# LightRetaggioSchema.net
KiCad netlist of a schematic drawn in EAGLE
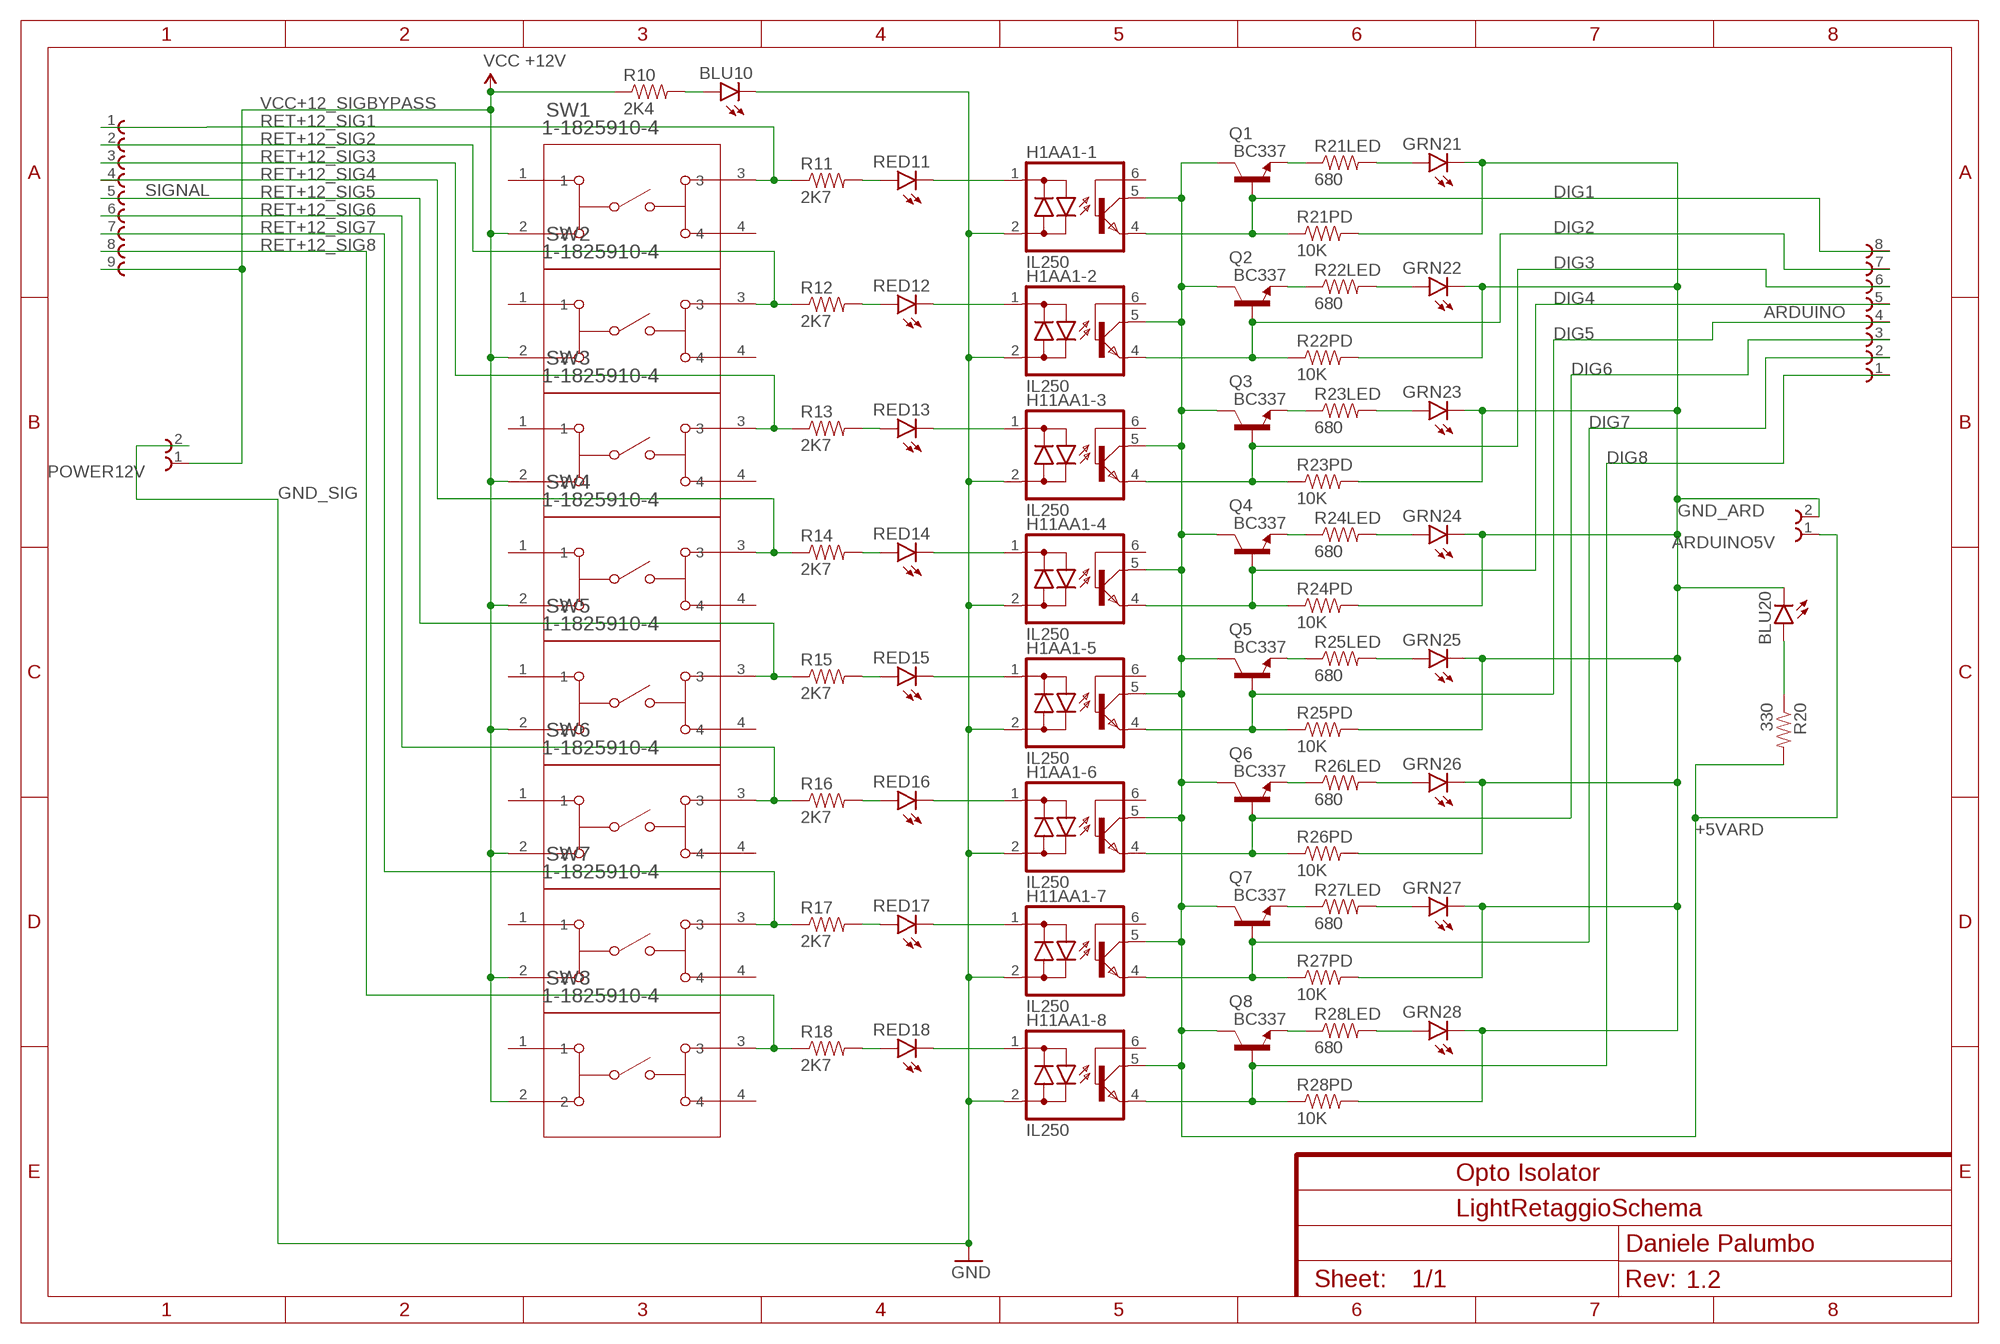
[diagram p0: schematic, sheet 1]

(export (version "E")
  (design (tool "Eeschema 10.0.6"))
  (components
    (comp (ref "ARDUINO")
      (value "691311500108")
      (footprint "eagle-import:691311500108")
      (libsource (lib "eagle-import") (part "691311500108"))
    )
    (comp (ref "ARDUINO5V")
      (value "691311500102")
      (footprint "eagle-import:691311500102")
      (fields (field (name "MF") "WURTH ELEKTRONIK"))
      (libsource (lib "eagle-import") (part "691311500102"))
    )
    (comp (ref "BLU10")
      (value "LED5MM")
      (footprint "eagle-import:LED5MM")
      (fields (field (name "MF") "ALCOSWITCH - TE CONNECTIVITY") (field (name "MPN") "FSM8JH"))
      (libsource (lib "eagle-import") (part "LED5MM"))
    )
    (comp (ref "BLU20")
      (value "LED5MM")
      (footprint "eagle-import:LED5MM")
      (fields (field (name "MF") "ALCOSWITCH - TE CONNECTIVITY") (field (name "MPN") "FSM8JH"))
      (libsource (lib "eagle-import") (part "LED5MM"))
    )
    (comp (ref "GRN21")
      (value "LED5MM")
      (footprint "eagle-import:LED5MM")
      (fields (field (name "MF") "ALCOSWITCH - TE CONNECTIVITY") (field (name "MPN") "FSM8JH"))
      (libsource (lib "eagle-import") (part "LED5MM"))
    )
    (comp (ref "GRN22")
      (value "LED5MM")
      (footprint "eagle-import:LED5MM")
      (fields (field (name "MF") "ALCOSWITCH - TE CONNECTIVITY") (field (name "MPN") "FSM8JH"))
      (libsource (lib "eagle-import") (part "LED5MM"))
    )
    (comp (ref "GRN23")
      (value "LED5MM")
      (footprint "eagle-import:LED5MM")
      (fields (field (name "MF") "ALCOSWITCH - TE CONNECTIVITY") (field (name "MPN") "FSM8JH"))
      (libsource (lib "eagle-import") (part "LED5MM"))
    )
    (comp (ref "GRN24")
      (value "LED5MM")
      (footprint "eagle-import:LED5MM")
      (fields (field (name "MF") "ALCOSWITCH - TE CONNECTIVITY") (field (name "MPN") "FSM8JH"))
      (libsource (lib "eagle-import") (part "LED5MM"))
    )
    (comp (ref "GRN25")
      (value "LED5MM")
      (footprint "eagle-import:LED5MM")
      (fields (field (name "MF") "ALCOSWITCH - TE CONNECTIVITY") (field (name "MPN") "FSM8JH"))
      (libsource (lib "eagle-import") (part "LED5MM"))
    )
    (comp (ref "GRN26")
      (value "LED5MM")
      (footprint "eagle-import:LED5MM")
      (fields (field (name "MF") "ALCOSWITCH - TE CONNECTIVITY") (field (name "MPN") "FSM8JH"))
      (libsource (lib "eagle-import") (part "LED5MM"))
    )
    (comp (ref "GRN27")
      (value "LED5MM")
      (footprint "eagle-import:LED5MM")
      (fields (field (name "MF") "ALCOSWITCH - TE CONNECTIVITY") (field (name "MPN") "FSM8JH"))
      (libsource (lib "eagle-import") (part "LED5MM"))
    )
    (comp (ref "GRN28")
      (value "LED5MM")
      (footprint "eagle-import:LED5MM")
      (fields (field (name "MF") "ALCOSWITCH - TE CONNECTIVITY") (field (name "MPN") "FSM8JH"))
      (libsource (lib "eagle-import") (part "LED5MM"))
    )
    (comp (ref "H1AA1-1")
      (value "IL250")
      (footprint "eagle-import:DIL06")
      (fields (field (name "MF") "VISHAY/TELEFUNKEN") (field (name "OC_FARNELL") "unknown"))
      (libsource (lib "eagle-import") (part "IL250"))
    )
    (comp (ref "H1AA1-2")
      (value "IL250")
      (footprint "eagle-import:DIL06")
      (fields (field (name "MF") "VISHAY/TELEFUNKEN") (field (name "OC_FARNELL") "unknown"))
      (libsource (lib "eagle-import") (part "IL250"))
    )
    (comp (ref "H1AA1-5")
      (value "IL250")
      (footprint "eagle-import:DIL06")
      (fields (field (name "MF") "VISHAY/TELEFUNKEN") (field (name "OC_FARNELL") "unknown"))
      (libsource (lib "eagle-import") (part "IL250"))
    )
    (comp (ref "H1AA1-6")
      (value "IL250")
      (footprint "eagle-import:DIL06")
      (fields (field (name "MF") "VISHAY/TELEFUNKEN") (field (name "OC_FARNELL") "unknown"))
      (libsource (lib "eagle-import") (part "IL250"))
    )
    (comp (ref "H11AA1-3")
      (value "IL250")
      (footprint "eagle-import:DIL06")
      (fields (field (name "MF") "VISHAY/TELEFUNKEN") (field (name "OC_FARNELL") "unknown"))
      (libsource (lib "eagle-import") (part "IL250"))
    )
    (comp (ref "H11AA1-4")
      (value "IL250")
      (footprint "eagle-import:DIL06")
      (fields (field (name "MF") "VISHAY/TELEFUNKEN") (field (name "OC_FARNELL") "unknown"))
      (libsource (lib "eagle-import") (part "IL250"))
    )
    (comp (ref "H11AA1-7")
      (value "IL250")
      (footprint "eagle-import:DIL06")
      (fields (field (name "MF") "VISHAY/TELEFUNKEN") (field (name "OC_FARNELL") "unknown"))
      (libsource (lib "eagle-import") (part "IL250"))
    )
    (comp (ref "H11AA1-8")
      (value "IL250")
      (footprint "eagle-import:DIL06")
      (fields (field (name "MF") "VISHAY/TELEFUNKEN") (field (name "OC_FARNELL") "unknown"))
      (libsource (lib "eagle-import") (part "IL250"))
    )
    (comp (ref "POWER12V")
      (value "691311500102")
      (footprint "eagle-import:691311500102")
      (fields (field (name "MF") "WURTH ELEKTRONIK"))
      (libsource (lib "eagle-import") (part "691311500102"))
    )
    (comp (ref "Q1")
      (value "BC337")
      (footprint "eagle-import:TO-92")
      (libsource (lib "eagle-import") (part "TRANS_NPN-P2N2222A"))
    )
    (comp (ref "Q2")
      (value "BC337")
      (footprint "eagle-import:TO-92")
      (libsource (lib "eagle-import") (part "TRANS_NPN-P2N2222A"))
    )
    (comp (ref "Q3")
      (value "BC337")
      (footprint "eagle-import:TO-92")
      (libsource (lib "eagle-import") (part "TRANS_NPN-P2N2222A"))
    )
    (comp (ref "Q4")
      (value "BC337")
      (footprint "eagle-import:TO-92")
      (libsource (lib "eagle-import") (part "TRANS_NPN-P2N2222A"))
    )
    (comp (ref "Q5")
      (value "BC337")
      (footprint "eagle-import:TO-92")
      (libsource (lib "eagle-import") (part "TRANS_NPN-P2N2222A"))
    )
    (comp (ref "Q6")
      (value "BC337")
      (footprint "eagle-import:TO-92")
      (libsource (lib "eagle-import") (part "TRANS_NPN-P2N2222A"))
    )
    (comp (ref "Q7")
      (value "BC337")
      (footprint "eagle-import:TO-92")
      (libsource (lib "eagle-import") (part "TRANS_NPN-P2N2222A"))
    )
    (comp (ref "Q8")
      (value "BC337")
      (footprint "eagle-import:TO-92")
      (libsource (lib "eagle-import") (part "TRANS_NPN-P2N2222A"))
    )
    (comp (ref "R10")
      (value "2K4")
      (footprint "eagle-import:AXIAL-0.4")
      (libsource (lib "eagle-import") (part "RESISTORPTH-1/4W"))
    )
    (comp (ref "R11")
      (value "2K7")
      (footprint "eagle-import:AXIAL-0.4")
      (libsource (lib "eagle-import") (part "RESISTORPTH-1/4W"))
    )
    (comp (ref "R12")
      (value "2K7")
      (footprint "eagle-import:AXIAL-0.4")
      (libsource (lib "eagle-import") (part "RESISTORPTH-1/4W"))
    )
    (comp (ref "R13")
      (value "2K7")
      (footprint "eagle-import:AXIAL-0.4")
      (libsource (lib "eagle-import") (part "RESISTORPTH-1/4W"))
    )
    (comp (ref "R14")
      (value "2K7")
      (footprint "eagle-import:AXIAL-0.4")
      (libsource (lib "eagle-import") (part "RESISTORPTH-1/4W"))
    )
    (comp (ref "R15")
      (value "2K7")
      (footprint "eagle-import:AXIAL-0.4")
      (libsource (lib "eagle-import") (part "RESISTORPTH-1/4W"))
    )
    (comp (ref "R16")
      (value "2K7")
      (footprint "eagle-import:AXIAL-0.4")
      (libsource (lib "eagle-import") (part "RESISTORPTH-1/4W"))
    )
    (comp (ref "R17")
      (value "2K7")
      (footprint "eagle-import:AXIAL-0.4")
      (libsource (lib "eagle-import") (part "RESISTORPTH-1/4W"))
    )
    (comp (ref "R18")
      (value "2K7")
      (footprint "eagle-import:AXIAL-0.4")
      (libsource (lib "eagle-import") (part "RESISTORPTH-1/4W"))
    )
    (comp (ref "R20")
      (value "330")
      (footprint "eagle-import:AXIAL-0.4")
      (libsource (lib "eagle-import") (part "RESISTORPTH-1/4W"))
    )
    (comp (ref "R21LED")
      (value "680")
      (footprint "eagle-import:AXIAL-0.4")
      (libsource (lib "eagle-import") (part "RESISTORPTH-1/4W"))
    )
    (comp (ref "R21PD")
      (value "10K")
      (footprint "eagle-import:AXIAL-0.4")
      (libsource (lib "eagle-import") (part "RESISTORPTH-1/4W"))
    )
    (comp (ref "R22LED")
      (value "680")
      (footprint "eagle-import:AXIAL-0.4")
      (libsource (lib "eagle-import") (part "RESISTORPTH-1/4W"))
    )
    (comp (ref "R22PD")
      (value "10K")
      (footprint "eagle-import:AXIAL-0.4")
      (libsource (lib "eagle-import") (part "RESISTORPTH-1/4W"))
    )
    (comp (ref "R23LED")
      (value "680")
      (footprint "eagle-import:AXIAL-0.4")
      (libsource (lib "eagle-import") (part "RESISTORPTH-1/4W"))
    )
    (comp (ref "R23PD")
      (value "10K")
      (footprint "eagle-import:AXIAL-0.4")
      (libsource (lib "eagle-import") (part "RESISTORPTH-1/4W"))
    )
    (comp (ref "R24LED")
      (value "680")
      (footprint "eagle-import:AXIAL-0.4")
      (libsource (lib "eagle-import") (part "RESISTORPTH-1/4W"))
    )
    (comp (ref "R24PD")
      (value "10K")
      (footprint "eagle-import:AXIAL-0.4")
      (libsource (lib "eagle-import") (part "RESISTORPTH-1/4W"))
    )
    (comp (ref "R25LED")
      (value "680")
      (footprint "eagle-import:AXIAL-0.4")
      (libsource (lib "eagle-import") (part "RESISTORPTH-1/4W"))
    )
    (comp (ref "R25PD")
      (value "10K")
      (footprint "eagle-import:AXIAL-0.4")
      (libsource (lib "eagle-import") (part "RESISTORPTH-1/4W"))
    )
    (comp (ref "R26LED")
      (value "680")
      (footprint "eagle-import:AXIAL-0.4")
      (libsource (lib "eagle-import") (part "RESISTORPTH-1/4W"))
    )
    (comp (ref "R26PD")
      (value "10K")
      (footprint "eagle-import:AXIAL-0.4")
      (libsource (lib "eagle-import") (part "RESISTORPTH-1/4W"))
    )
    (comp (ref "R27LED")
      (value "680")
      (footprint "eagle-import:AXIAL-0.4")
      (libsource (lib "eagle-import") (part "RESISTORPTH-1/4W"))
    )
    (comp (ref "R27PD")
      (value "10K")
      (footprint "eagle-import:AXIAL-0.4")
      (libsource (lib "eagle-import") (part "RESISTORPTH-1/4W"))
    )
    (comp (ref "R28LED")
      (value "680")
      (footprint "eagle-import:AXIAL-0.4")
      (libsource (lib "eagle-import") (part "RESISTORPTH-1/4W"))
    )
    (comp (ref "R28PD")
      (value "10K")
      (footprint "eagle-import:AXIAL-0.4")
      (libsource (lib "eagle-import") (part "RESISTORPTH-1/4W"))
    )
    (comp (ref "RED11")
      (value "LED5MM")
      (footprint "eagle-import:LED5MM")
      (fields (field (name "MF") "ALCOSWITCH - TE CONNECTIVITY") (field (name "MPN") "FSM8JH"))
      (libsource (lib "eagle-import") (part "LED5MM"))
    )
    (comp (ref "RED12")
      (value "LED5MM")
      (footprint "eagle-import:LED5MM")
      (fields (field (name "MF") "ALCOSWITCH - TE CONNECTIVITY") (field (name "MPN") "FSM8JH"))
      (libsource (lib "eagle-import") (part "LED5MM"))
    )
    (comp (ref "RED13")
      (value "LED5MM")
      (footprint "eagle-import:LED5MM")
      (fields (field (name "MF") "ALCOSWITCH - TE CONNECTIVITY") (field (name "MPN") "FSM8JH"))
      (libsource (lib "eagle-import") (part "LED5MM"))
    )
    (comp (ref "RED14")
      (value "LED5MM")
      (footprint "eagle-import:LED5MM")
      (fields (field (name "MF") "ALCOSWITCH - TE CONNECTIVITY") (field (name "MPN") "FSM8JH"))
      (libsource (lib "eagle-import") (part "LED5MM"))
    )
    (comp (ref "RED15")
      (value "LED5MM")
      (footprint "eagle-import:LED5MM")
      (fields (field (name "MF") "ALCOSWITCH - TE CONNECTIVITY") (field (name "MPN") "FSM8JH"))
      (libsource (lib "eagle-import") (part "LED5MM"))
    )
    (comp (ref "RED16")
      (value "LED5MM")
      (footprint "eagle-import:LED5MM")
      (fields (field (name "MF") "ALCOSWITCH - TE CONNECTIVITY") (field (name "MPN") "FSM8JH"))
      (libsource (lib "eagle-import") (part "LED5MM"))
    )
    (comp (ref "RED17")
      (value "LED5MM")
      (footprint "eagle-import:LED5MM")
      (fields (field (name "MF") "ALCOSWITCH - TE CONNECTIVITY") (field (name "MPN") "FSM8JH"))
      (libsource (lib "eagle-import") (part "LED5MM"))
    )
    (comp (ref "RED18")
      (value "LED5MM")
      (footprint "eagle-import:LED5MM")
      (fields (field (name "MF") "ALCOSWITCH - TE CONNECTIVITY") (field (name "MPN") "FSM8JH"))
      (libsource (lib "eagle-import") (part "LED5MM"))
    )
    (comp (ref "SIGNAL")
      (value "691311500109")
      (footprint "eagle-import:691311500109")
      (libsource (lib "eagle-import") (part "691311500109"))
    )
    (comp (ref "SW1")
      (value "1-1825910-4")
      (footprint "eagle-import:SW4_1825910-D")
      (fields (field (name "COPYRIGHT") "Copyright (C) 2016 Accelerated Designs. All rights reserved"))
      (libsource (lib "eagle-import") (part "1-1825910-4"))
    )
    (comp (ref "SW2")
      (value "1-1825910-4")
      (footprint "eagle-import:SW4_1825910-D")
      (fields (field (name "COPYRIGHT") "Copyright (C) 2016 Accelerated Designs. All rights reserved"))
      (libsource (lib "eagle-import") (part "1-1825910-4"))
    )
    (comp (ref "SW3")
      (value "1-1825910-4")
      (footprint "eagle-import:SW4_1825910-D")
      (fields (field (name "COPYRIGHT") "Copyright (C) 2016 Accelerated Designs. All rights reserved"))
      (libsource (lib "eagle-import") (part "1-1825910-4"))
    )
    (comp (ref "SW4")
      (value "1-1825910-4")
      (footprint "eagle-import:SW4_1825910-D")
      (fields (field (name "COPYRIGHT") "Copyright (C) 2016 Accelerated Designs. All rights reserved"))
      (libsource (lib "eagle-import") (part "1-1825910-4"))
    )
    (comp (ref "SW5")
      (value "1-1825910-4")
      (footprint "eagle-import:SW4_1825910-D")
      (fields (field (name "COPYRIGHT") "Copyright (C) 2016 Accelerated Designs. All rights reserved"))
      (libsource (lib "eagle-import") (part "1-1825910-4"))
    )
    (comp (ref "SW6")
      (value "1-1825910-4")
      (footprint "eagle-import:SW4_1825910-D")
      (fields (field (name "COPYRIGHT") "Copyright (C) 2016 Accelerated Designs. All rights reserved"))
      (libsource (lib "eagle-import") (part "1-1825910-4"))
    )
    (comp (ref "SW7")
      (value "1-1825910-4")
      (footprint "eagle-import:SW4_1825910-D")
      (fields (field (name "COPYRIGHT") "Copyright (C) 2016 Accelerated Designs. All rights reserved"))
      (libsource (lib "eagle-import") (part "1-1825910-4"))
    )
    (comp (ref "SW8")
      (value "1-1825910-4")
      (footprint "eagle-import:SW4_1825910-D")
      (fields (field (name "COPYRIGHT") "Copyright (C) 2016 Accelerated Designs. All rights reserved"))
      (libsource (lib "eagle-import") (part "1-1825910-4"))
    )
  )
  (nets
    (net (code "1") (name "/+5VARD") (class "Default")
      (node (ref "ARDUINO5V") (pin "1") (pinfunction "1_1") (pintype "passive"))
      (node (ref "H11AA1-3") (pin "5") (pinfunction "C_5") (pintype "passive"))
      (node (ref "H11AA1-4") (pin "5") (pinfunction "C_5") (pintype "passive"))
      (node (ref "H11AA1-7") (pin "5") (pinfunction "C_5") (pintype "passive"))
      (node (ref "H11AA1-8") (pin "5") (pinfunction "C_5") (pintype "passive"))
      (node (ref "H1AA1-1") (pin "5") (pinfunction "C_5") (pintype "passive"))
      (node (ref "H1AA1-2") (pin "5") (pinfunction "C_5") (pintype "passive"))
      (node (ref "H1AA1-5") (pin "5") (pinfunction "C_5") (pintype "passive"))
      (node (ref "H1AA1-6") (pin "5") (pinfunction "C_5") (pintype "passive"))
      (node (ref "Q1") (pin "1") (pinfunction "C_1") (pintype "passive"))
      (node (ref "Q2") (pin "1") (pinfunction "C_1") (pintype "passive"))
      (node (ref "Q3") (pin "1") (pinfunction "C_1") (pintype "passive"))
      (node (ref "Q4") (pin "1") (pinfunction "C_1") (pintype "passive"))
      (node (ref "Q5") (pin "1") (pinfunction "C_1") (pintype "passive"))
      (node (ref "Q6") (pin "1") (pinfunction "C_1") (pintype "passive"))
      (node (ref "Q7") (pin "1") (pinfunction "C_1") (pintype "passive"))
      (node (ref "Q8") (pin "1") (pinfunction "C_1") (pintype "passive"))
      (node (ref "R20") (pin "P$2") (pinfunction "2_P$2") (pintype "passive"))
    )
    (net (code "2") (name "/DIG1") (class "Default")
      (node (ref "ARDUINO") (pin "8") (pinfunction "8_8") (pintype "passive"))
      (node (ref "H1AA1-1") (pin "4") (pinfunction "E_4") (pintype "passive"))
      (node (ref "Q1") (pin "2") (pinfunction "B_2") (pintype "passive"))
      (node (ref "R21PD") (pin "P$1") (pinfunction "1_P$1") (pintype "passive"))
    )
    (net (code "3") (name "/DIG2") (class "Default")
      (node (ref "ARDUINO") (pin "7") (pinfunction "7_7") (pintype "passive"))
      (node (ref "H1AA1-2") (pin "4") (pinfunction "E_4") (pintype "passive"))
      (node (ref "Q2") (pin "2") (pinfunction "B_2") (pintype "passive"))
      (node (ref "R22PD") (pin "P$1") (pinfunction "1_P$1") (pintype "passive"))
    )
    (net (code "4") (name "/DIG3") (class "Default")
      (node (ref "ARDUINO") (pin "6") (pinfunction "6_6") (pintype "passive"))
      (node (ref "H11AA1-3") (pin "4") (pinfunction "E_4") (pintype "passive"))
      (node (ref "Q3") (pin "2") (pinfunction "B_2") (pintype "passive"))
      (node (ref "R23PD") (pin "P$1") (pinfunction "1_P$1") (pintype "passive"))
    )
    (net (code "5") (name "/DIG4") (class "Default")
      (node (ref "ARDUINO") (pin "5") (pinfunction "5_5") (pintype "passive"))
      (node (ref "H11AA1-4") (pin "4") (pinfunction "E_4") (pintype "passive"))
      (node (ref "Q4") (pin "2") (pinfunction "B_2") (pintype "passive"))
      (node (ref "R24PD") (pin "P$1") (pinfunction "1_P$1") (pintype "passive"))
    )
    (net (code "6") (name "/DIG5") (class "Default")
      (node (ref "ARDUINO") (pin "4") (pinfunction "4_4") (pintype "passive"))
      (node (ref "H1AA1-5") (pin "4") (pinfunction "E_4") (pintype "passive"))
      (node (ref "Q5") (pin "2") (pinfunction "B_2") (pintype "passive"))
      (node (ref "R25PD") (pin "P$1") (pinfunction "1_P$1") (pintype "passive"))
    )
    (net (code "7") (name "/DIG6") (class "Default")
      (node (ref "ARDUINO") (pin "3") (pinfunction "3_3") (pintype "passive"))
      (node (ref "H1AA1-6") (pin "4") (pinfunction "E_4") (pintype "passive"))
      (node (ref "Q6") (pin "2") (pinfunction "B_2") (pintype "passive"))
      (node (ref "R26PD") (pin "P$1") (pinfunction "1_P$1") (pintype "passive"))
    )
    (net (code "8") (name "/DIG7") (class "Default")
      (node (ref "ARDUINO") (pin "2") (pinfunction "2_2") (pintype "passive"))
      (node (ref "H11AA1-7") (pin "4") (pinfunction "E_4") (pintype "passive"))
      (node (ref "Q7") (pin "2") (pinfunction "B_2") (pintype "passive"))
      (node (ref "R27PD") (pin "P$1") (pinfunction "1_P$1") (pintype "passive"))
    )
    (net (code "9") (name "/DIG8") (class "Default")
      (node (ref "ARDUINO") (pin "1") (pinfunction "1_1") (pintype "passive"))
      (node (ref "H11AA1-8") (pin "4") (pinfunction "E_4") (pintype "passive"))
      (node (ref "Q8") (pin "2") (pinfunction "B_2") (pintype "passive"))
      (node (ref "R28PD") (pin "P$1") (pinfunction "1_P$1") (pintype "passive"))
    )
    (net (code "10") (name "/GND_ARD") (class "Default")
      (node (ref "ARDUINO5V") (pin "2") (pinfunction "2_2") (pintype "passive"))
      (node (ref "BLU20") (pin "K") (pinfunction "C_K") (pintype "passive"))
      (node (ref "GRN21") (pin "K") (pinfunction "C_K") (pintype "passive"))
      (node (ref "GRN22") (pin "K") (pinfunction "C_K") (pintype "passive"))
      (node (ref "GRN23") (pin "K") (pinfunction "C_K") (pintype "passive"))
      (node (ref "GRN24") (pin "K") (pinfunction "C_K") (pintype "passive"))
      (node (ref "GRN25") (pin "K") (pinfunction "C_K") (pintype "passive"))
      (node (ref "GRN26") (pin "K") (pinfunction "C_K") (pintype "passive"))
      (node (ref "GRN27") (pin "K") (pinfunction "C_K") (pintype "passive"))
      (node (ref "GRN28") (pin "K") (pinfunction "C_K") (pintype "passive"))
      (node (ref "R21PD") (pin "P$2") (pinfunction "2_P$2") (pintype "passive"))
      (node (ref "R22PD") (pin "P$2") (pinfunction "2_P$2") (pintype "passive"))
      (node (ref "R23PD") (pin "P$2") (pinfunction "2_P$2") (pintype "passive"))
      (node (ref "R24PD") (pin "P$2") (pinfunction "2_P$2") (pintype "passive"))
      (node (ref "R25PD") (pin "P$2") (pinfunction "2_P$2") (pintype "passive"))
      (node (ref "R26PD") (pin "P$2") (pinfunction "2_P$2") (pintype "passive"))
      (node (ref "R27PD") (pin "P$2") (pinfunction "2_P$2") (pintype "passive"))
      (node (ref "R28PD") (pin "P$2") (pinfunction "2_P$2") (pintype "passive"))
    )
    (net (code "11") (name "/RET+12_SIG1") (class "Default")
      (node (ref "R11") (pin "P$1") (pinfunction "1_P$1") (pintype "passive"))
      (node (ref "SIGNAL") (pin "1") (pinfunction "1_1") (pintype "passive"))
      (node (ref "SW1") (pin "3") (pinfunction "3_3") (pintype "passive"))
    )
    (net (code "12") (name "/RET+12_SIG2") (class "Default")
      (node (ref "R12") (pin "P$1") (pinfunction "1_P$1") (pintype "passive"))
      (node (ref "SIGNAL") (pin "2") (pinfunction "2_2") (pintype "passive"))
      (node (ref "SW2") (pin "3") (pinfunction "3_3") (pintype "passive"))
    )
    (net (code "13") (name "/RET+12_SIG3") (class "Default")
      (node (ref "R13") (pin "P$1") (pinfunction "1_P$1") (pintype "passive"))
      (node (ref "SIGNAL") (pin "3") (pinfunction "3_3") (pintype "passive"))
      (node (ref "SW3") (pin "3") (pinfunction "3_3") (pintype "passive"))
    )
    (net (code "14") (name "/RET+12_SIG4") (class "Default")
      (node (ref "R14") (pin "P$1") (pinfunction "1_P$1") (pintype "passive"))
      (node (ref "SIGNAL") (pin "4") (pinfunction "4_4") (pintype "passive"))
      (node (ref "SW4") (pin "3") (pinfunction "3_3") (pintype "passive"))
    )
    (net (code "15") (name "/RET+12_SIG5") (class "Default")
      (node (ref "R15") (pin "P$1") (pinfunction "1_P$1") (pintype "passive"))
      (node (ref "SIGNAL") (pin "5") (pinfunction "5_5") (pintype "passive"))
      (node (ref "SW5") (pin "3") (pinfunction "3_3") (pintype "passive"))
    )
    (net (code "16") (name "/RET+12_SIG6") (class "Default")
      (node (ref "R16") (pin "P$1") (pinfunction "1_P$1") (pintype "passive"))
      (node (ref "SIGNAL") (pin "6") (pinfunction "6_6") (pintype "passive"))
      (node (ref "SW6") (pin "3") (pinfunction "3_3") (pintype "passive"))
    )
    (net (code "17") (name "/RET+12_SIG7") (class "Default")
      (node (ref "R17") (pin "P$1") (pinfunction "1_P$1") (pintype "passive"))
      (node (ref "SIGNAL") (pin "7") (pinfunction "7_7") (pintype "passive"))
      (node (ref "SW7") (pin "3") (pinfunction "3_3") (pintype "passive"))
    )
    (net (code "18") (name "/RET+12_SIG8") (class "Default")
      (node (ref "R18") (pin "P$1") (pinfunction "1_P$1") (pintype "passive"))
      (node (ref "SIGNAL") (pin "8") (pinfunction "8_8") (pintype "passive"))
      (node (ref "SW8") (pin "3") (pinfunction "3_3") (pintype "passive"))
    )
    (net (code "19") (name "GND") (class "Default")
      (node (ref "BLU10") (pin "K") (pinfunction "C_K") (pintype "passive"))
      (node (ref "H11AA1-3") (pin "2") (pinfunction "AC2_2") (pintype "passive"))
      (node (ref "H11AA1-4") (pin "2") (pinfunction "AC2_2") (pintype "passive"))
      (node (ref "H11AA1-7") (pin "2") (pinfunction "AC2_2") (pintype "passive"))
      (node (ref "H11AA1-8") (pin "2") (pinfunction "AC2_2") (pintype "passive"))
      (node (ref "H1AA1-1") (pin "2") (pinfunction "AC2_2") (pintype "passive"))
      (node (ref "H1AA1-2") (pin "2") (pinfunction "AC2_2") (pintype "passive"))
      (node (ref "H1AA1-5") (pin "2") (pinfunction "AC2_2") (pintype "passive"))
      (node (ref "H1AA1-6") (pin "2") (pinfunction "AC2_2") (pintype "passive"))
      (node (ref "POWER12V") (pin "2") (pinfunction "2_2") (pintype "passive"))
    )
    (net (code "20") (name "Net-(H1AA1-1-AC1)") (class "Default")
      (node (ref "H1AA1-1") (pin "1") (pinfunction "AC1_1") (pintype "passive"))
      (node (ref "RED11") (pin "K") (pinfunction "C_K") (pintype "passive"))
    )
    (net (code "21") (name "Net-(H1AA1-2-AC1)") (class "Default")
      (node (ref "H1AA1-2") (pin "1") (pinfunction "AC1_1") (pintype "passive"))
      (node (ref "RED12") (pin "K") (pinfunction "C_K") (pintype "passive"))
    )
    (net (code "22") (name "Net-(H1AA1-5-AC1)") (class "Default")
      (node (ref "H1AA1-5") (pin "1") (pinfunction "AC1_1") (pintype "passive"))
      (node (ref "RED15") (pin "K") (pinfunction "C_K") (pintype "passive"))
    )
    (net (code "23") (name "Net-(H1AA1-6-AC1)") (class "Default")
      (node (ref "H1AA1-6") (pin "1") (pinfunction "AC1_1") (pintype "passive"))
      (node (ref "RED16") (pin "K") (pinfunction "C_K") (pintype "passive"))
    )
    (net (code "24") (name "Net-(H11AA1-3-AC1)") (class "Default")
      (node (ref "H11AA1-3") (pin "1") (pinfunction "AC1_1") (pintype "passive"))
      (node (ref "RED13") (pin "K") (pinfunction "C_K") (pintype "passive"))
    )
    (net (code "25") (name "Net-(H11AA1-4-AC1)") (class "Default")
      (node (ref "H11AA1-4") (pin "1") (pinfunction "AC1_1") (pintype "passive"))
      (node (ref "RED14") (pin "K") (pinfunction "C_K") (pintype "passive"))
    )
    (net (code "26") (name "Net-(H11AA1-7-AC1)") (class "Default")
      (node (ref "H11AA1-7") (pin "1") (pinfunction "AC1_1") (pintype "passive"))
      (node (ref "RED17") (pin "K") (pinfunction "C_K") (pintype "passive"))
    )
    (net (code "27") (name "Net-(H11AA1-8-AC1)") (class "Default")
      (node (ref "H11AA1-8") (pin "1") (pinfunction "AC1_1") (pintype "passive"))
      (node (ref "RED18") (pin "K") (pinfunction "C_K") (pintype "passive"))
    )
    (net (code "28") (name "Net-(Q1-E)") (class "Default")
      (node (ref "Q1") (pin "3") (pinfunction "E_3") (pintype "passive"))
      (node (ref "R21LED") (pin "P$1") (pinfunction "1_P$1") (pintype "passive"))
    )
    (net (code "29") (name "Net-(Q2-E)") (class "Default")
      (node (ref "Q2") (pin "3") (pinfunction "E_3") (pintype "passive"))
      (node (ref "R22LED") (pin "P$1") (pinfunction "1_P$1") (pintype "passive"))
    )
    (net (code "30") (name "Net-(Q3-E)") (class "Default")
      (node (ref "Q3") (pin "3") (pinfunction "E_3") (pintype "passive"))
      (node (ref "R23LED") (pin "P$1") (pinfunction "1_P$1") (pintype "passive"))
    )
    (net (code "31") (name "Net-(Q4-E)") (class "Default")
      (node (ref "Q4") (pin "3") (pinfunction "E_3") (pintype "passive"))
      (node (ref "R24LED") (pin "P$1") (pinfunction "1_P$1") (pintype "passive"))
    )
    (net (code "32") (name "Net-(Q5-E)") (class "Default")
      (node (ref "Q5") (pin "3") (pinfunction "E_3") (pintype "passive"))
      (node (ref "R25LED") (pin "P$1") (pinfunction "1_P$1") (pintype "passive"))
    )
    (net (code "33") (name "Net-(Q6-E)") (class "Default")
      (node (ref "Q6") (pin "3") (pinfunction "E_3") (pintype "passive"))
      (node (ref "R26LED") (pin "P$1") (pinfunction "1_P$1") (pintype "passive"))
    )
    (net (code "34") (name "Net-(Q7-E)") (class "Default")
      (node (ref "Q7") (pin "3") (pinfunction "E_3") (pintype "passive"))
      (node (ref "R27LED") (pin "P$1") (pinfunction "1_P$1") (pintype "passive"))
    )
    (net (code "35") (name "Net-(Q8-E)") (class "Default")
      (node (ref "Q8") (pin "3") (pinfunction "E_3") (pintype "passive"))
      (node (ref "R28LED") (pin "P$1") (pinfunction "1_P$1") (pintype "passive"))
    )
    (net (code "36") (name "Net-(R10-2)") (class "Default")
      (node (ref "BLU10") (pin "A") (pinfunction "A_A") (pintype "passive"))
      (node (ref "R10") (pin "P$2") (pinfunction "2_P$2") (pintype "passive"))
    )
    (net (code "37") (name "Net-(R11-2)") (class "Default")
      (node (ref "R11") (pin "P$2") (pinfunction "2_P$2") (pintype "passive"))
      (node (ref "RED11") (pin "A") (pinfunction "A_A") (pintype "passive"))
    )
    (net (code "38") (name "Net-(R12-2)") (class "Default")
      (node (ref "R12") (pin "P$2") (pinfunction "2_P$2") (pintype "passive"))
      (node (ref "RED12") (pin "A") (pinfunction "A_A") (pintype "passive"))
    )
    (net (code "39") (name "Net-(R13-2)") (class "Default")
      (node (ref "R13") (pin "P$2") (pinfunction "2_P$2") (pintype "passive"))
      (node (ref "RED13") (pin "A") (pinfunction "A_A") (pintype "passive"))
    )
    (net (code "40") (name "Net-(R14-2)") (class "Default")
      (node (ref "R14") (pin "P$2") (pinfunction "2_P$2") (pintype "passive"))
      (node (ref "RED14") (pin "A") (pinfunction "A_A") (pintype "passive"))
    )
    (net (code "41") (name "Net-(R15-2)") (class "Default")
      (node (ref "R15") (pin "P$2") (pinfunction "2_P$2") (pintype "passive"))
      (node (ref "RED15") (pin "A") (pinfunction "A_A") (pintype "passive"))
    )
    (net (code "42") (name "Net-(R16-2)") (class "Default")
      (node (ref "R16") (pin "P$2") (pinfunction "2_P$2") (pintype "passive"))
      (node (ref "RED16") (pin "A") (pinfunction "A_A") (pintype "passive"))
    )
    (net (code "43") (name "Net-(R17-2)") (class "Default")
      (node (ref "R17") (pin "P$2") (pinfunction "2_P$2") (pintype "passive"))
      (node (ref "RED17") (pin "A") (pinfunction "A_A") (pintype "passive"))
    )
    (net (code "44") (name "Net-(R18-2)") (class "Default")
      (node (ref "R18") (pin "P$2") (pinfunction "2_P$2") (pintype "passive"))
      (node (ref "RED18") (pin "A") (pinfunction "A_A") (pintype "passive"))
    )
    (net (code "45") (name "Net-(R20-1)") (class "Default")
      (node (ref "BLU20") (pin "A") (pinfunction "A_A") (pintype "passive"))
      (node (ref "R20") (pin "P$1") (pinfunction "1_P$1") (pintype "passive"))
    )
    (net (code "46") (name "Net-(R21LED-2)") (class "Default")
      (node (ref "GRN21") (pin "A") (pinfunction "A_A") (pintype "passive"))
      (node (ref "R21LED") (pin "P$2") (pinfunction "2_P$2") (pintype "passive"))
    )
    (net (code "47") (name "Net-(R22LED-2)") (class "Default")
      (node (ref "GRN22") (pin "A") (pinfunction "A_A") (pintype "passive"))
      (node (ref "R22LED") (pin "P$2") (pinfunction "2_P$2") (pintype "passive"))
    )
    (net (code "48") (name "Net-(R23LED-2)") (class "Default")
      (node (ref "GRN23") (pin "A") (pinfunction "A_A") (pintype "passive"))
      (node (ref "R23LED") (pin "P$2") (pinfunction "2_P$2") (pintype "passive"))
    )
    (net (code "49") (name "Net-(R24LED-2)") (class "Default")
      (node (ref "GRN24") (pin "A") (pinfunction "A_A") (pintype "passive"))
      (node (ref "R24LED") (pin "P$2") (pinfunction "2_P$2") (pintype "passive"))
    )
    (net (code "50") (name "Net-(R25LED-2)") (class "Default")
      (node (ref "GRN25") (pin "A") (pinfunction "A_A") (pintype "passive"))
      (node (ref "R25LED") (pin "P$2") (pinfunction "2_P$2") (pintype "passive"))
    )
    (net (code "51") (name "Net-(R26LED-2)") (class "Default")
      (node (ref "GRN26") (pin "A") (pinfunction "A_A") (pintype "passive"))
      (node (ref "R26LED") (pin "P$2") (pinfunction "2_P$2") (pintype "passive"))
    )
    (net (code "52") (name "Net-(R27LED-2)") (class "Default")
      (node (ref "GRN27") (pin "A") (pinfunction "A_A") (pintype "passive"))
      (node (ref "R27LED") (pin "P$2") (pinfunction "2_P$2") (pintype "passive"))
    )
    (net (code "53") (name "Net-(R28LED-2)") (class "Default")
      (node (ref "GRN28") (pin "A") (pinfunction "A_A") (pintype "passive"))
      (node (ref "R28LED") (pin "P$2") (pinfunction "2_P$2") (pintype "passive"))
    )
    (net (code "54") (name "VCC +12V") (class "Default")
      (node (ref "POWER12V") (pin "1") (pinfunction "1_1") (pintype "passive"))
      (node (ref "R10") (pin "P$1") (pinfunction "1_P$1") (pintype "passive"))
      (node (ref "SIGNAL") (pin "9") (pinfunction "9_9") (pintype "passive"))
      (node (ref "SW1") (pin "2") (pinfunction "2_2") (pintype "passive"))
      (node (ref "SW2") (pin "2") (pinfunction "2_2") (pintype "passive"))
      (node (ref "SW3") (pin "2") (pinfunction "2_2") (pintype "passive"))
      (node (ref "SW4") (pin "2") (pinfunction "2_2") (pintype "passive"))
      (node (ref "SW5") (pin "2") (pinfunction "2_2") (pintype "passive"))
      (node (ref "SW6") (pin "2") (pinfunction "2_2") (pintype "passive"))
      (node (ref "SW7") (pin "2") (pinfunction "2_2") (pintype "passive"))
      (node (ref "SW8") (pin "2") (pinfunction "2_2") (pintype "passive"))
    )
    (net (code "55") (name "unconnected-(H1AA1-1-B-Pad6)") (class "Default")
      (node (ref "H1AA1-1") (pin "6") (pinfunction "B_6") (pintype "passive"))
    )
    (net (code "56") (name "unconnected-(H1AA1-2-B-Pad6)") (class "Default")
      (node (ref "H1AA1-2") (pin "6") (pinfunction "B_6") (pintype "passive"))
    )
    (net (code "57") (name "unconnected-(H1AA1-5-B-Pad6)") (class "Default")
      (node (ref "H1AA1-5") (pin "6") (pinfunction "B_6") (pintype "passive"))
    )
    (net (code "58") (name "unconnected-(H1AA1-6-B-Pad6)") (class "Default")
      (node (ref "H1AA1-6") (pin "6") (pinfunction "B_6") (pintype "passive"))
    )
    (net (code "59") (name "unconnected-(H11AA1-3-B-Pad6)") (class "Default")
      (node (ref "H11AA1-3") (pin "6") (pinfunction "B_6") (pintype "passive"))
    )
    (net (code "60") (name "unconnected-(H11AA1-4-B-Pad6)") (class "Default")
      (node (ref "H11AA1-4") (pin "6") (pinfunction "B_6") (pintype "passive"))
    )
    (net (code "61") (name "unconnected-(H11AA1-7-B-Pad6)") (class "Default")
      (node (ref "H11AA1-7") (pin "6") (pinfunction "B_6") (pintype "passive"))
    )
    (net (code "62") (name "unconnected-(H11AA1-8-B-Pad6)") (class "Default")
      (node (ref "H11AA1-8") (pin "6") (pinfunction "B_6") (pintype "passive"))
    )
    (net (code "63") (name "unconnected-(SW1-Pad1)") (class "Default")
      (node (ref "SW1") (pin "1") (pinfunction "1_1") (pintype "passive"))
    )
    (net (code "64") (name "unconnected-(SW1-Pad4)") (class "Default")
      (node (ref "SW1") (pin "4") (pinfunction "4_4") (pintype "passive"))
    )
    (net (code "65") (name "unconnected-(SW2-Pad1)") (class "Default")
      (node (ref "SW2") (pin "1") (pinfunction "1_1") (pintype "passive"))
    )
    (net (code "66") (name "unconnected-(SW2-Pad4)") (class "Default")
      (node (ref "SW2") (pin "4") (pinfunction "4_4") (pintype "passive"))
    )
    (net (code "67") (name "unconnected-(SW3-Pad1)") (class "Default")
      (node (ref "SW3") (pin "1") (pinfunction "1_1") (pintype "passive"))
    )
    (net (code "68") (name "unconnected-(SW3-Pad4)") (class "Default")
      (node (ref "SW3") (pin "4") (pinfunction "4_4") (pintype "passive"))
    )
    (net (code "69") (name "unconnected-(SW4-Pad1)") (class "Default")
      (node (ref "SW4") (pin "1") (pinfunction "1_1") (pintype "passive"))
    )
    (net (code "70") (name "unconnected-(SW4-Pad4)") (class "Default")
      (node (ref "SW4") (pin "4") (pinfunction "4_4") (pintype "passive"))
    )
    (net (code "71") (name "unconnected-(SW5-Pad1)") (class "Default")
      (node (ref "SW5") (pin "1") (pinfunction "1_1") (pintype "passive"))
    )
    (net (code "72") (name "unconnected-(SW5-Pad4)") (class "Default")
      (node (ref "SW5") (pin "4") (pinfunction "4_4") (pintype "passive"))
    )
    (net (code "73") (name "unconnected-(SW6-Pad1)") (class "Default")
      (node (ref "SW6") (pin "1") (pinfunction "1_1") (pintype "passive"))
    )
    (net (code "74") (name "unconnected-(SW6-Pad4)") (class "Default")
      (node (ref "SW6") (pin "4") (pinfunction "4_4") (pintype "passive"))
    )
    (net (code "75") (name "unconnected-(SW7-Pad1)") (class "Default")
      (node (ref "SW7") (pin "1") (pinfunction "1_1") (pintype "passive"))
    )
    (net (code "76") (name "unconnected-(SW7-Pad4)") (class "Default")
      (node (ref "SW7") (pin "4") (pinfunction "4_4") (pintype "passive"))
    )
    (net (code "77") (name "unconnected-(SW8-Pad1)") (class "Default")
      (node (ref "SW8") (pin "1") (pinfunction "1_1") (pintype "passive"))
    )
    (net (code "78") (name "unconnected-(SW8-Pad4)") (class "Default")
      (node (ref "SW8") (pin "4") (pinfunction "4_4") (pintype "passive"))
    )
  )
)
